# Camera_Schematic.net
KiCad netlist of a schematic drawn in Altium Designer
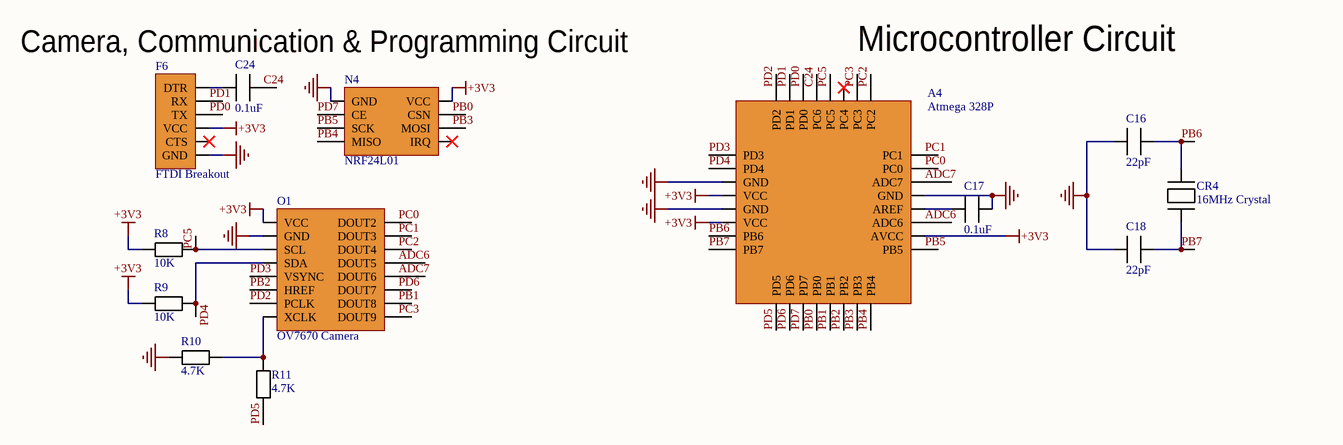
[diagram p0: Camera Schematic.SchDoc]

(export (version "E")
  (design (tool "Eeschema 10.0.6"))
  (components
    (comp (ref "A4")
      (value "Atmega 328P")
      (footprint "ATMega328P")
      (description "IC MCU 8BIT 32KB FLASH 32TQFP")
      (fields
        (field (name "MANUFACTURER") "Microchip")
        (field (name "MANUFACTURER PART NUMBER") "ATMEGA328PB-AUR")
      )
      (libsource (lib "Schematic Library") (part "ATMEGA328PB-AUR"))
    )
    (comp (ref "C16")
      (value "22pF")
      (footprint "22pF Capacitor")
      (description "Cap Ceramic 22pF 50V C0G 5% SMD 0603 125C Paper T/R")
      (fields
        (field (name "MANUFACTURER") "Kyocera AVX")
        (field (name "MANUFACTURER PART NUMBER") "06035A220JAT2A")
      )
      (libsource (lib "Schematic Library") (part "06035A220JAT2A"))
    )
    (comp (ref "C17")
      (value "0.1uF")
      (footprint "0.1uF Capacitor")
      (description "CAP CER 0.1UF 25V X7R 0603")
      (fields
        (field (name "MANUFACTURER") "Kyocera AVX")
        (field (name "MANUFACTURER PART NUMBER") "06033C104KAT4A")
      )
      (libsource (lib "Schematic Library") (part "06033C104KAT4A"))
    )
    (comp (ref "C18")
      (value "22pF")
      (footprint "22pF Capacitor")
      (description "Cap Ceramic 22pF 50V C0G 5% SMD 0603 125C Paper T/R")
      (fields
        (field (name "MANUFACTURER") "Kyocera AVX")
        (field (name "MANUFACTURER PART NUMBER") "06035A220JAT2A")
      )
      (libsource (lib "Schematic Library") (part "06035A220JAT2A"))
    )
    (comp (ref "C24")
      (value "0.1uF")
      (footprint "0.1uF Capacitor")
      (description "CAP CER 0.1UF 25V X7R 0603")
      (fields
        (field (name "MANUFACTURER") "Kyocera AVX")
        (field (name "MANUFACTURER PART NUMBER") "06033C104KAT4A")
      )
      (libsource (lib "Schematic Library") (part "06033C104KAT4A"))
    )
    (comp (ref "CR4")
      (value "16MHz Crystal")
      (footprint "16MHz Crystal")
      (description "CRYSTAL 16.0000MHZ 20PF SMD")
      (fields
        (field (name "MANUFACTURER") "ECS International")
        (field (name "MANUFACTURER PART NUMBER") "ECS-160-20-3X-TR")
      )
      (libsource (lib "Schematic Library") (part "ECS-160-20-3X-TR"))
    )
    (comp (ref "F6")
      (value "FTDI Breakout")
      (footprint "FTDI")
      (description "FTDI USB to TTL serial converter module")
      (libsource (lib "Schematic Library") (part "FTDI"))
    )
    (comp (ref "N4")
      (value "NRF24L01")
      (footprint "NRF24L01")
      (description "3.3V NRF24L01 WIRELESS RF MODULE")
      (libsource (lib "Schematic Library") (part "NRF24L01"))
    )
    (comp (ref "O1")
      (value "OV7670 Camera")
      (footprint "OV7670 Camera Module")
      (description "CMOS OV7670 Camera Module\r\n1/6-Inch 0.3-Megapixel Module")
      (libsource (lib "Schematic Library") (part "OV7670 Camera Module"))
    )
    (comp (ref "R8")
      (value "10K")
      (footprint "10K Resistor")
      (description "RES 10K OHM 1% 1/8W 0603")
      (fields
        (field (name "MANUFACTURER") "Stackpole Electronics")
        (field (name "MANUFACTURER PART NUMBER") "RNCP0603FTD10K0")
      )
      (libsource (lib "Schematic Library") (part "RNCP0603FTD10K0"))
    )
    (comp (ref "R9")
      (value "10K")
      (footprint "10K Resistor")
      (description "RES 10K OHM 1% 1/8W 0603")
      (fields
        (field (name "MANUFACTURER") "Stackpole Electronics")
        (field (name "MANUFACTURER PART NUMBER") "RNCP0603FTD10K0")
      )
      (libsource (lib "Schematic Library") (part "RNCP0603FTD10K0"))
    )
    (comp (ref "R10")
      (value "4.7K")
      (footprint "4.7K Resistor")
      (description "Res Thick Film 0603 4.7K Ohm 1% 1/10W 100ppm/C Molded SMD SMD Paper T/R")
      (fields
        (field (name "MANUFACTURER") "Stackpole Electronics")
        (field (name "MANUFACTURER PART NUMBER") "RMCF0603FT4K70")
      )
      (libsource (lib "Schematic Library") (part "RMCF0603FT4K70"))
    )
    (comp (ref "R11")
      (value "4.7K")
      (footprint "4.7K Resistor")
      (description "Res Thick Film 0603 4.7K Ohm 1% 1/10W 100ppm/C Molded SMD SMD Paper T/R")
      (fields
        (field (name "MANUFACTURER") "Stackpole Electronics")
        (field (name "MANUFACTURER PART NUMBER") "RMCF0603FT4K70")
      )
      (libsource (lib "Schematic Library") (part "RMCF0603FT4K70"))
    )
  )
  (nets
    (net (code "1") (name "+3V3") (class "Default")
      (node (ref "A4") (pin "18") (pinfunction "AVCC_18") (pintype "passive"))
      (node (ref "A4") (pin "4") (pinfunction "VCC_4") (pintype "passive"))
      (node (ref "A4") (pin "6") (pinfunction "VCC_6") (pintype "passive"))
      (node (ref "F6") (pin "4") (pinfunction "VCC_4") (pintype "passive"))
      (node (ref "N4") (pin "5") (pinfunction "VCC_5") (pintype "passive"))
      (node (ref "O1") (pin "1") (pinfunction "VCC_1") (pintype "passive"))
      (node (ref "R8") (pin "1") (pinfunction "1_1") (pintype "passive"))
      (node (ref "R9") (pin "1") (pinfunction "1_1") (pintype "passive"))
    )
    (net (code "2") (name "/ADC6") (class "Default")
      (node (ref "A4") (pin "19") (pinfunction "ADC6_19") (pintype "passive"))
      (node (ref "O1") (pin "13") (pinfunction "DOUT5_13") (pintype "passive"))
    )
    (net (code "3") (name "/ADC7") (class "Default")
      (node (ref "A4") (pin "22") (pinfunction "ADC7_22") (pintype "passive"))
      (node (ref "O1") (pin "12") (pinfunction "DOUT6_12") (pintype "passive"))
    )
    (net (code "4") (name "/C24") (class "Default")
      (node (ref "A4") (pin "29") (pinfunction "PC6_29") (pintype "passive"))
      (node (ref "C24") (pin "2") (pinfunction "2_2") (pintype "passive"))
    )
    (net (code "5") (name "/PB0") (class "Default")
      (node (ref "A4") (pin "12") (pinfunction "PB0_12") (pintype "passive"))
      (node (ref "N4") (pin "6") (pinfunction "CSN_6") (pintype "passive"))
    )
    (net (code "6") (name "/PB1") (class "Default")
      (node (ref "A4") (pin "13") (pinfunction "PB1_13") (pintype "passive"))
      (node (ref "O1") (pin "10") (pinfunction "DOUT8_10") (pintype "passive"))
    )
    (net (code "7") (name "/PB2") (class "Default")
      (node (ref "A4") (pin "14") (pinfunction "PB2_14") (pintype "passive"))
      (node (ref "O1") (pin "6") (pinfunction "HREF_6") (pintype "passive"))
    )
    (net (code "8") (name "/PB3") (class "Default")
      (node (ref "A4") (pin "15") (pinfunction "PB3_15") (pintype "passive"))
      (node (ref "N4") (pin "7") (pinfunction "MOSI_7") (pintype "passive"))
    )
    (net (code "9") (name "/PB4") (class "Default")
      (node (ref "A4") (pin "16") (pinfunction "PB4_16") (pintype "passive"))
      (node (ref "N4") (pin "4") (pinfunction "MISO_4") (pintype "passive"))
    )
    (net (code "10") (name "/PB5") (class "Default")
      (node (ref "A4") (pin "17") (pinfunction "PB5_17") (pintype "passive"))
      (node (ref "N4") (pin "3") (pinfunction "SCK_3") (pintype "passive"))
    )
    (net (code "11") (name "/PB6") (class "Default")
      (node (ref "A4") (pin "7") (pinfunction "PB6_7") (pintype "passive"))
      (node (ref "C16") (pin "2") (pinfunction "2_2") (pintype "passive"))
      (node (ref "CR4") (pin "2") (pinfunction "2_2") (pintype "passive"))
    )
    (net (code "12") (name "/PB7") (class "Default")
      (node (ref "A4") (pin "8") (pinfunction "PB7_8") (pintype "passive"))
      (node (ref "C18") (pin "2") (pinfunction "2_2") (pintype "passive"))
      (node (ref "CR4") (pin "1") (pinfunction "1_1") (pintype "passive"))
    )
    (net (code "13") (name "/PC0") (class "Default")
      (node (ref "A4") (pin "23") (pinfunction "PC0_23") (pintype "passive"))
      (node (ref "O1") (pin "16") (pinfunction "DOUT2_16") (pintype "passive"))
    )
    (net (code "14") (name "/PC1") (class "Default")
      (node (ref "A4") (pin "24") (pinfunction "PC1_24") (pintype "passive"))
      (node (ref "O1") (pin "15") (pinfunction "DOUT3_15") (pintype "passive"))
    )
    (net (code "15") (name "/PC2") (class "Default")
      (node (ref "A4") (pin "25") (pinfunction "PC2_25") (pintype "passive"))
      (node (ref "O1") (pin "14") (pinfunction "DOUT4_14") (pintype "passive"))
    )
    (net (code "16") (name "/PC3") (class "Default")
      (node (ref "A4") (pin "26") (pinfunction "PC3_26") (pintype "passive"))
      (node (ref "O1") (pin "9") (pinfunction "DOUT9_9") (pintype "passive"))
    )
    (net (code "17") (name "/PC5") (class "Default")
      (node (ref "A4") (pin "28") (pinfunction "PC5_28") (pintype "passive"))
      (node (ref "O1") (pin "3") (pinfunction "SCL_3") (pintype "passive"))
      (node (ref "R8") (pin "2") (pinfunction "2_2") (pintype "passive"))
    )
    (net (code "18") (name "/PD0") (class "Default")
      (node (ref "A4") (pin "30") (pinfunction "PD0_30") (pintype "passive"))
      (node (ref "F6") (pin "3") (pinfunction "TX_3") (pintype "passive"))
    )
    (net (code "19") (name "/PD1") (class "Default")
      (node (ref "A4") (pin "31") (pinfunction "PD1_31") (pintype "passive"))
      (node (ref "F6") (pin "2") (pinfunction "RX_2") (pintype "passive"))
    )
    (net (code "20") (name "/PD2") (class "Default")
      (node (ref "A4") (pin "32") (pinfunction "PD2_32") (pintype "passive"))
      (node (ref "O1") (pin "7") (pinfunction "PCLK_7") (pintype "passive"))
    )
    (net (code "21") (name "/PD3") (class "Default")
      (node (ref "A4") (pin "1") (pinfunction "PD3_1") (pintype "passive"))
      (node (ref "O1") (pin "5") (pinfunction "VSYNC_5") (pintype "passive"))
    )
    (net (code "22") (name "/PD4") (class "Default")
      (node (ref "A4") (pin "2") (pinfunction "PD4_2") (pintype "passive"))
      (node (ref "O1") (pin "4") (pinfunction "SDA_4") (pintype "passive"))
      (node (ref "R9") (pin "2") (pinfunction "2_2") (pintype "passive"))
    )
    (net (code "23") (name "/PD5") (class "Default")
      (node (ref "A4") (pin "9") (pinfunction "PD5_9") (pintype "passive"))
      (node (ref "R11") (pin "1") (pinfunction "1_1") (pintype "passive"))
    )
    (net (code "24") (name "/PD6") (class "Default")
      (node (ref "A4") (pin "10") (pinfunction "PD6_10") (pintype "passive"))
      (node (ref "O1") (pin "11") (pinfunction "DOUT7_11") (pintype "passive"))
    )
    (net (code "25") (name "/PD7") (class "Default")
      (node (ref "A4") (pin "11") (pinfunction "PD7_11") (pintype "passive"))
      (node (ref "N4") (pin "2") (pinfunction "CE_2") (pintype "passive"))
    )
    (net (code "26") (name "GND") (class "Default")
      (node (ref "A4") (pin "21") (pinfunction "GND_21") (pintype "passive"))
      (node (ref "A4") (pin "3") (pinfunction "GND_3") (pintype "passive"))
      (node (ref "A4") (pin "5") (pinfunction "GND_5") (pintype "passive"))
      (node (ref "C16") (pin "1") (pinfunction "1_1") (pintype "passive"))
      (node (ref "C17") (pin "2") (pinfunction "2_2") (pintype "passive"))
      (node (ref "C18") (pin "1") (pinfunction "1_1") (pintype "passive"))
      (node (ref "F6") (pin "6") (pinfunction "GND_6") (pintype "passive"))
      (node (ref "N4") (pin "1") (pinfunction "GND_1") (pintype "passive"))
      (node (ref "O1") (pin "2") (pinfunction "GND_2") (pintype "passive"))
      (node (ref "R10") (pin "1") (pinfunction "1_1") (pintype "passive"))
    )
    (net (code "27") (name "Net-(A4-AREF)") (class "Default")
      (node (ref "A4") (pin "20") (pinfunction "AREF_20") (pintype "passive"))
      (node (ref "C17") (pin "1") (pinfunction "1_1") (pintype "passive"))
    )
    (net (code "28") (name "Net-(F6-DTR)") (class "Default")
      (node (ref "C24") (pin "1") (pinfunction "1_1") (pintype "passive"))
      (node (ref "F6") (pin "1") (pinfunction "DTR_1") (pintype "passive"))
    )
    (net (code "29") (name "Net-(O1-XCLK)") (class "Default")
      (node (ref "O1") (pin "8") (pinfunction "XCLK_8") (pintype "passive"))
      (node (ref "R10") (pin "2") (pinfunction "2_2") (pintype "passive"))
      (node (ref "R11") (pin "2") (pinfunction "2_2") (pintype "passive"))
    )
    (net (code "30") (name "unconnected-(A4-PC4-Pad27)") (class "Default")
      (node (ref "A4") (pin "27") (pinfunction "PC4_27") (pintype "passive+no_connect"))
    )
    (net (code "31") (name "unconnected-(F6-CTS-Pad5)") (class "Default")
      (node (ref "F6") (pin "5") (pinfunction "CTS_5") (pintype "passive+no_connect"))
    )
    (net (code "32") (name "unconnected-(N4-IRQ-Pad8)") (class "Default")
      (node (ref "N4") (pin "8") (pinfunction "IRQ_8") (pintype "passive+no_connect"))
    )
  )
)
